# femtoBeacon_BT5_coin.net
KiCad netlist of a schematic drawn in EAGLE
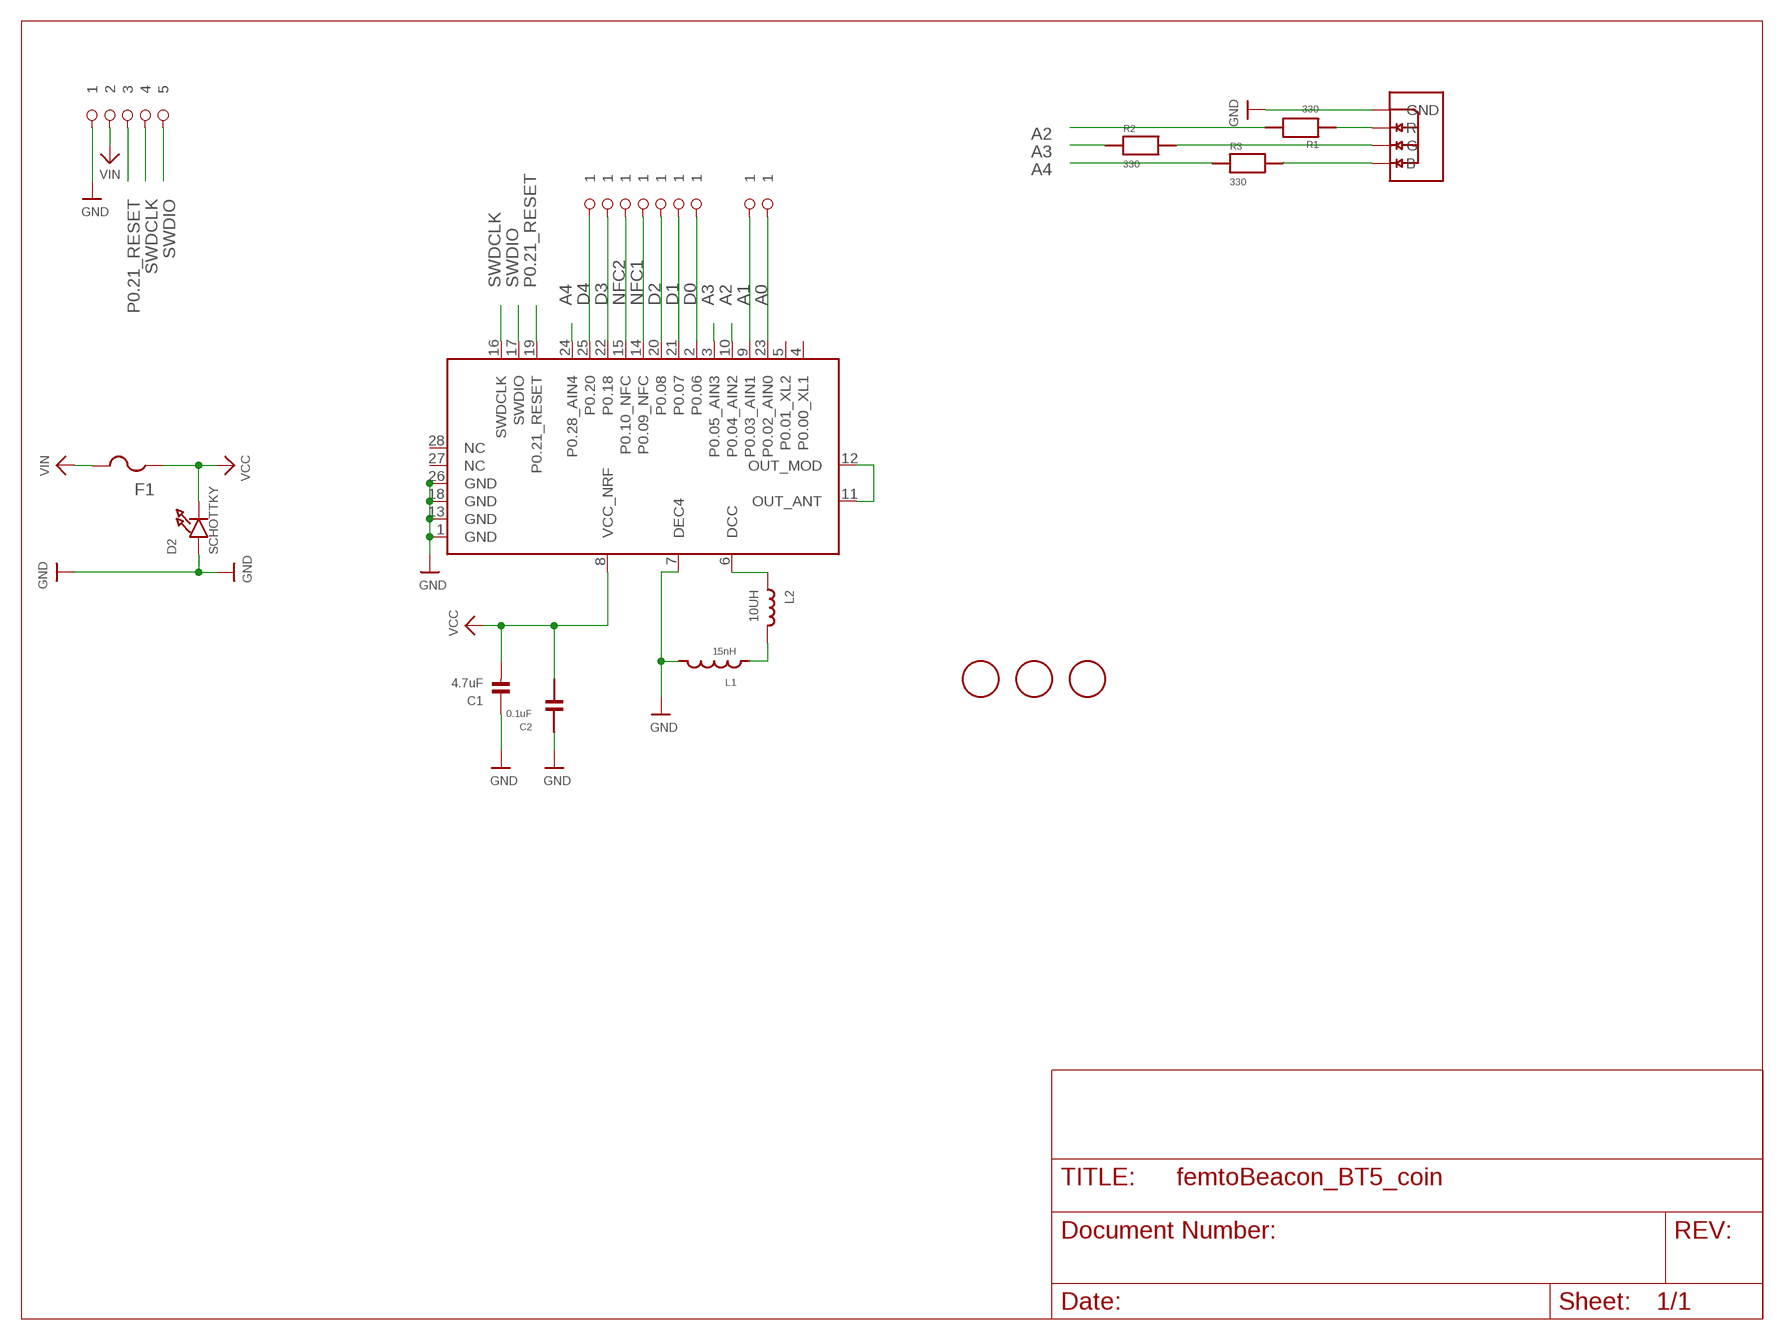
[diagram p0: schematic, sheet 1]

(export (version "E")
  (design (tool "Eeschema 10.0.6"))
  (components
    (comp (ref "C1")
      (value "4.7uF")
      (footprint "eagle-import:_0402MP")
      (libsource (lib "eagle-import") (part "CAP_CERAMIC_0402MP"))
    )
    (comp (ref "C2")
      (value "0.1uF")
      (footprint "eagle-import:PART")
      (libsource (lib "eagle-import") (part "CAPACITOR_0201"))
    )
    (comp (ref "D2")
      (value "SCHOTTKY")
      (footprint "eagle-import:CHIPLED_0603_NOOUTLINE")
      (libsource (lib "eagle-import") (part "LED0603_NOOUTLINE"))
    )
    (comp (ref "F1")
      (value "PTCFUSE-1206")
      (footprint "eagle-import:R1206")
      (libsource (lib "eagle-import") (part "PTCFUSE-1206"))
    )
    (comp (ref "FID1")
      (value "FIDUCIAL")
      (footprint "eagle-import:FIDUCIAL_1MM")
      (libsource (lib "eagle-import") (part "FIDUCIAL"))
    )
    (comp (ref "FID2")
      (value "FIDUCIAL")
      (footprint "eagle-import:FIDUCIAL_1MM")
      (libsource (lib "eagle-import") (part "FIDUCIAL"))
    )
    (comp (ref "FID3")
      (value "FIDUCIAL")
      (footprint "eagle-import:FIDUCIAL_1MM")
      (libsource (lib "eagle-import") (part "FIDUCIAL"))
    )
    (comp (ref "IC")
      (value "TY_BLE_EYSHSNZWZ")
      (footprint "eagle-import:MODULE")
      (libsource (lib "eagle-import") (part "TY_BLE_EYSHSNZWZ"))
    )
    (comp (ref "L1")
      (value "15nH")
      (footprint "eagle-import:PART")
      (libsource (lib "eagle-import") (part "INDUCTOR_FIXED_0201"))
    )
    (comp (ref "L2")
      (value "10UH")
      (footprint "eagle-import:_0402MP")
      (libsource (lib "eagle-import") (part "INDUCTOR_0402MP"))
    )
    (comp (ref "LED1")
      (value "LRTB_R48G")
      (footprint "eagle-import:LRTB_R48G")
      (libsource (lib "eagle-import") (part "LRTB_R48G"))
    )
    (comp (ref "R1")
      (value "330")
      (footprint "eagle-import:PART")
      (libsource (lib "eagle-import") (part "RESISTOR_0201"))
    )
    (comp (ref "R2")
      (value "330")
      (footprint "eagle-import:PART")
      (libsource (lib "eagle-import") (part "RESISTOR_0201"))
    )
    (comp (ref "R3")
      (value "330")
      (footprint "eagle-import:PART")
      (libsource (lib "eagle-import") (part "RESISTOR_0201"))
    )
    (comp (ref "U$6")
      (value "1X5_ROUND")
      (footprint "eagle-import:1X5_ROUND")
      (libsource (lib "eagle-import") (part "1X5_ROUND"))
    )
    (comp (ref "U$16")
      (value "1X1_ROUND_MM")
      (footprint "eagle-import:1X1_ROUND_MM")
      (libsource (lib "eagle-import") (part "1X1_ROUND_MM"))
    )
    (comp (ref "U$17")
      (value "1X1_ROUND_MM")
      (footprint "eagle-import:1X1_ROUND_MM")
      (libsource (lib "eagle-import") (part "1X1_ROUND_MM"))
    )
    (comp (ref "U$18")
      (value "1X1_ROUND_MM")
      (footprint "eagle-import:1X1_ROUND_MM")
      (libsource (lib "eagle-import") (part "1X1_ROUND_MM"))
    )
    (comp (ref "U$19")
      (value "1X1_ROUND_MM")
      (footprint "eagle-import:1X1_ROUND_MM")
      (libsource (lib "eagle-import") (part "1X1_ROUND_MM"))
    )
    (comp (ref "U$20")
      (value "1X1_ROUND_MM")
      (footprint "eagle-import:1X1_ROUND_MM")
      (libsource (lib "eagle-import") (part "1X1_ROUND_MM"))
    )
    (comp (ref "U$21")
      (value "1X1_ROUND_MM")
      (footprint "eagle-import:1X1_ROUND_MM")
      (libsource (lib "eagle-import") (part "1X1_ROUND_MM"))
    )
    (comp (ref "U$22")
      (value "1X1_ROUND_MM")
      (footprint "eagle-import:1X1_ROUND_MM")
      (libsource (lib "eagle-import") (part "1X1_ROUND_MM"))
    )
    (comp (ref "U$23")
      (value "1X1_ROUND_MM")
      (footprint "eagle-import:1X1_ROUND_MM")
      (libsource (lib "eagle-import") (part "1X1_ROUND_MM"))
    )
    (comp (ref "U$24")
      (value "1X1_ROUND_MM")
      (footprint "eagle-import:1X1_ROUND_MM")
      (libsource (lib "eagle-import") (part "1X1_ROUND_MM"))
    )
  )
  (nets
    (net (code "1") (name "/A0") (class "Default")
      (node (ref "IC") (pin "23") (pinfunction "P0.02_AIN0_23") (pintype "bidirectional"))
      (node (ref "U$16") (pin "P$1") (pinfunction "1_P$1") (pintype "bidirectional"))
    )
    (net (code "2") (name "/A1") (class "Default")
      (node (ref "IC") (pin "9") (pinfunction "P0.03_AIN1_9") (pintype "bidirectional"))
      (node (ref "U$17") (pin "P$1") (pinfunction "1_P$1") (pintype "bidirectional"))
    )
    (net (code "3") (name "/A2") (class "Default")
      (node (ref "IC") (pin "10") (pinfunction "P0.04_AIN2_10") (pintype "bidirectional"))
      (node (ref "R1") (pin "2") (pinfunction "2_2") (pintype "bidirectional"))
    )
    (net (code "4") (name "/A3") (class "Default")
      (node (ref "IC") (pin "3") (pinfunction "P0.05_AIN3_3") (pintype "bidirectional"))
      (node (ref "R2") (pin "1") (pinfunction "1_1") (pintype "bidirectional"))
    )
    (net (code "5") (name "/A4") (class "Default")
      (node (ref "IC") (pin "24") (pinfunction "P0.28_AIN4_24") (pintype "bidirectional"))
      (node (ref "R3") (pin "1") (pinfunction "1_1") (pintype "bidirectional"))
    )
    (net (code "6") (name "/D0") (class "Default")
      (node (ref "IC") (pin "2") (pinfunction "P0.06_2") (pintype "bidirectional"))
      (node (ref "U$18") (pin "P$1") (pinfunction "1_P$1") (pintype "bidirectional"))
    )
    (net (code "7") (name "/D1") (class "Default")
      (node (ref "IC") (pin "21") (pinfunction "P0.07_21") (pintype "bidirectional"))
      (node (ref "U$19") (pin "P$1") (pinfunction "1_P$1") (pintype "bidirectional"))
    )
    (net (code "8") (name "/D2") (class "Default")
      (node (ref "IC") (pin "20") (pinfunction "P0.08_20") (pintype "bidirectional"))
      (node (ref "U$20") (pin "P$1") (pinfunction "1_P$1") (pintype "bidirectional"))
    )
    (net (code "9") (name "/D3") (class "Default")
      (node (ref "IC") (pin "22") (pinfunction "P0.18_22") (pintype "bidirectional"))
      (node (ref "U$23") (pin "P$1") (pinfunction "1_P$1") (pintype "bidirectional"))
    )
    (net (code "10") (name "/D4") (class "Default")
      (node (ref "IC") (pin "25") (pinfunction "P0.20_25") (pintype "bidirectional"))
      (node (ref "U$24") (pin "P$1") (pinfunction "1_P$1") (pintype "bidirectional"))
    )
    (net (code "11") (name "/NFC1") (class "Default")
      (node (ref "IC") (pin "14") (pinfunction "P0.09_NFC_14") (pintype "bidirectional"))
      (node (ref "U$21") (pin "P$1") (pinfunction "1_P$1") (pintype "bidirectional"))
    )
    (net (code "12") (name "/NFC2") (class "Default")
      (node (ref "IC") (pin "15") (pinfunction "P0.10_NFC_15") (pintype "bidirectional"))
      (node (ref "U$22") (pin "P$1") (pinfunction "1_P$1") (pintype "bidirectional"))
    )
    (net (code "13") (name "/P0.21_RESET") (class "Default")
      (node (ref "IC") (pin "19") (pinfunction "P0.21_RESET_19") (pintype "bidirectional"))
      (node (ref "U$6") (pin "P$3") (pinfunction "3_P$3") (pintype "bidirectional"))
    )
    (net (code "14") (name "/SWDCLK") (class "Default")
      (node (ref "IC") (pin "16") (pinfunction "SWDCLK_16") (pintype "bidirectional"))
      (node (ref "U$6") (pin "P$4") (pinfunction "4_P$4") (pintype "bidirectional"))
    )
    (net (code "15") (name "/SWDIO") (class "Default")
      (node (ref "IC") (pin "17") (pinfunction "SWDIO_17") (pintype "bidirectional"))
      (node (ref "U$6") (pin "P$5") (pinfunction "5_P$5") (pintype "bidirectional"))
    )
    (net (code "16") (name "GND") (class "Default")
      (node (ref "C1") (pin "1") (pinfunction "P$1_1") (pintype "passive"))
      (node (ref "C2") (pin "1") (pinfunction "P$1_1") (pintype "bidirectional"))
      (node (ref "D2") (pin "A") (pinfunction "A_A") (pintype "passive"))
      (node (ref "IC") (pin "1") (pinfunction "GND_1") (pintype "bidirectional"))
      (node (ref "IC") (pin "13") (pinfunction "GND_13") (pintype "bidirectional"))
      (node (ref "IC") (pin "18") (pinfunction "GND_18") (pintype "bidirectional"))
      (node (ref "IC") (pin "26") (pinfunction "GND_26") (pintype "bidirectional"))
      (node (ref "IC") (pin "7") (pinfunction "DEC4_7") (pintype "bidirectional"))
      (node (ref "L1") (pin "2") (pinfunction "P$2_2") (pintype "bidirectional"))
      (node (ref "LED1") (pin "1") (pinfunction "GND_1") (pintype "bidirectional"))
      (node (ref "U$6") (pin "P$1") (pinfunction "1_P$1") (pintype "bidirectional"))
    )
    (net (code "17") (name "Net-(IC-DCC)") (class "Default")
      (node (ref "IC") (pin "6") (pinfunction "DCC_6") (pintype "bidirectional"))
      (node (ref "L2") (pin "1") (pinfunction "1_1") (pintype "passive"))
    )
    (net (code "18") (name "Net-(IC-OUT_ANT)") (class "Default")
      (node (ref "IC") (pin "11") (pinfunction "OUT_ANT_11") (pintype "bidirectional"))
      (node (ref "IC") (pin "12") (pinfunction "OUT_MOD_12") (pintype "bidirectional"))
    )
    (net (code "19") (name "Net-(L1-P$1)") (class "Default")
      (node (ref "L1") (pin "1") (pinfunction "P$1_1") (pintype "bidirectional"))
      (node (ref "L2") (pin "2") (pinfunction "2_2") (pintype "passive"))
    )
    (net (code "20") (name "Net-(LED1-B)") (class "Default")
      (node (ref "LED1") (pin "4") (pinfunction "B_4") (pintype "bidirectional"))
      (node (ref "R3") (pin "2") (pinfunction "2_2") (pintype "bidirectional"))
    )
    (net (code "21") (name "Net-(LED1-G)") (class "Default")
      (node (ref "LED1") (pin "3") (pinfunction "G_3") (pintype "bidirectional"))
      (node (ref "R2") (pin "2") (pinfunction "2_2") (pintype "bidirectional"))
    )
    (net (code "22") (name "Net-(LED1-R)") (class "Default")
      (node (ref "LED1") (pin "2") (pinfunction "R_2") (pintype "bidirectional"))
      (node (ref "R1") (pin "1") (pinfunction "1_1") (pintype "bidirectional"))
    )
    (net (code "23") (name "VCC") (class "Default")
      (node (ref "C1") (pin "2") (pinfunction "P$2_2") (pintype "passive"))
      (node (ref "C2") (pin "2") (pinfunction "P$2_2") (pintype "bidirectional"))
      (node (ref "D2") (pin "C") (pinfunction "C_C") (pintype "passive"))
      (node (ref "F1") (pin "1") (pinfunction "1_1") (pintype "passive"))
      (node (ref "IC") (pin "8") (pinfunction "VCC_NRF_8") (pintype "bidirectional"))
    )
    (net (code "24") (name "VIN") (class "Default")
      (node (ref "F1") (pin "2") (pinfunction "2_2") (pintype "passive"))
      (node (ref "U$6") (pin "P$2") (pinfunction "2_P$2") (pintype "bidirectional"))
    )
    (net (code "25") (name "unconnected-(IC-NC-Pad27)") (class "Default")
      (node (ref "IC") (pin "27") (pinfunction "NC_27") (pintype "bidirectional"))
    )
    (net (code "26") (name "unconnected-(IC-NC-Pad28)") (class "Default")
      (node (ref "IC") (pin "28") (pinfunction "NC_28") (pintype "bidirectional"))
    )
    (net (code "27") (name "unconnected-(IC-P0.00_XL1-Pad4)") (class "Default")
      (node (ref "IC") (pin "4") (pinfunction "P0.00_XL1_4") (pintype "bidirectional"))
    )
    (net (code "28") (name "unconnected-(IC-P0.01_XL2-Pad5)") (class "Default")
      (node (ref "IC") (pin "5") (pinfunction "P0.01_XL2_5") (pintype "bidirectional"))
    )
  )
)
